# Loader.net
KiCad netlist of a schematic drawn in EAGLE
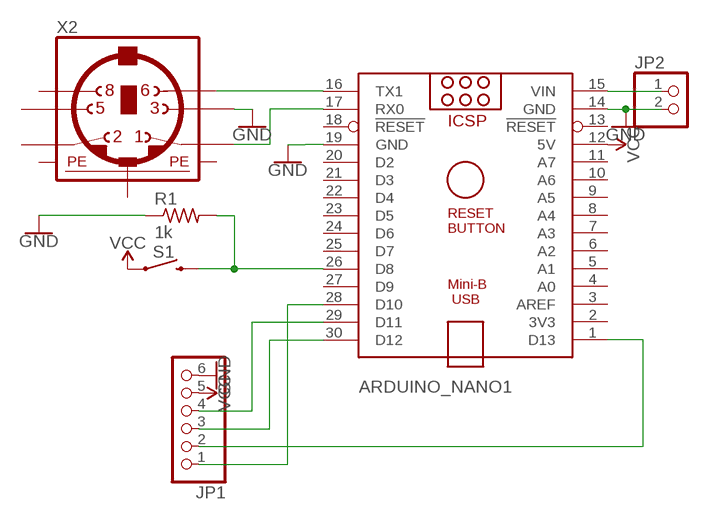
[diagram p0: schematic, sheet 1]

(export (version "E")
  (design (tool "Eeschema 10.0.6"))
  (components
    (comp (ref "ARDUINO_NANO1")
      (value "ARDUINO_NANO")
      (footprint "eagle-import:ARDUINO_NANO")
      (libsource (lib "eagle-import") (part "ARDUINO_NANO"))
    )
    (comp (ref "JP1")
      (value "PINHD-1X6")
      (footprint "eagle-import:1X06")
      (libsource (lib "eagle-import") (part "PINHD-1X6"))
    )
    (comp (ref "JP2")
      (value "PINHD-1X2")
      (footprint "eagle-import:1X02")
      (libsource (lib "eagle-import") (part "PINHD-1X2"))
    )
    (comp (ref "R1")
      (value "1k")
      (footprint "eagle-import:0204_7")
      (libsource (lib "eagle-import") (part "R-US_0204/7"))
    )
    (comp (ref "S1")
      (value "MOMENTARY-SWITCH-SPST-PTH-6.0MM")
      (footprint "eagle-import:TACTILE_SWITCH_PTH_6.0MM")
      (libsource (lib "eagle-import") (part "MOMENTARY-SWITCH-SPST-PTH-6.0MM"))
    )
    (comp (ref "X2")
      (value "MINI_DIN_6")
      (footprint "eagle-import:M_DIN6")
      (libsource (lib "eagle-import") (part "MINI_DIN_6"))
    )
  )
  (nets
    (net (code "1") (name "/PE1") (class "Default")
      (node (ref "X2") (pin "SH1") (pinfunction "PE1_SH1") (pintype "power_in"))
    )
    (net (code "2") (name "/PE2") (class "Default")
      (node (ref "X2") (pin "SH2") (pinfunction "PE2_SH2") (pintype "power_in"))
    )
    (net (code "3") (name "/PE3") (class "Default")
      (node (ref "X2") (pin "SH3") (pinfunction "PE3_SH3") (pintype "power_in"))
    )
    (net (code "4") (name "GND") (class "Default")
      (node (ref "ARDUINO_NANO1") (pin "14") (pinfunction "GND_14") (pintype "power_in"))
      (node (ref "ARDUINO_NANO1") (pin "19") (pinfunction "GND_19") (pintype "power_in"))
      (node (ref "JP1") (pin "6") (pinfunction "6_6") (pintype "passive"))
      (node (ref "JP2") (pin "2") (pinfunction "2_2") (pintype "passive"))
      (node (ref "R1") (pin "1") (pinfunction "1_1") (pintype "passive"))
      (node (ref "X2") (pin "3") (pinfunction "3_3") (pintype "passive"))
    )
    (net (code "5") (name "Net-(ARDUINO_NANO1-D8)") (class "Default")
      (node (ref "ARDUINO_NANO1") (pin "26") (pinfunction "D8_26") (pintype "bidirectional"))
      (node (ref "R1") (pin "2") (pinfunction "2_2") (pintype "passive"))
      (node (ref "S1") (pin "3") (pinfunction "2_3") (pintype "passive"))
    )
    (net (code "6") (name "Net-(ARDUINO_NANO1-D10)") (class "Default")
      (node (ref "ARDUINO_NANO1") (pin "28") (pinfunction "D10_28") (pintype "bidirectional"))
      (node (ref "JP1") (pin "1") (pinfunction "1_1") (pintype "passive"))
    )
    (net (code "7") (name "Net-(ARDUINO_NANO1-D11)") (class "Default")
      (node (ref "ARDUINO_NANO1") (pin "29") (pinfunction "D11_29") (pintype "bidirectional"))
      (node (ref "JP1") (pin "4") (pinfunction "4_4") (pintype "passive"))
    )
    (net (code "8") (name "Net-(ARDUINO_NANO1-D12)") (class "Default")
      (node (ref "ARDUINO_NANO1") (pin "30") (pinfunction "D12_30") (pintype "bidirectional"))
      (node (ref "JP1") (pin "3") (pinfunction "3_3") (pintype "passive"))
    )
    (net (code "9") (name "Net-(ARDUINO_NANO1-D13)") (class "Default")
      (node (ref "ARDUINO_NANO1") (pin "1") (pinfunction "D13_1") (pintype "bidirectional"))
      (node (ref "JP1") (pin "2") (pinfunction "2_2") (pintype "passive"))
    )
    (net (code "10") (name "Net-(ARDUINO_NANO1-RX0)") (class "Default")
      (node (ref "ARDUINO_NANO1") (pin "17") (pinfunction "RX0_17") (pintype "bidirectional"))
      (node (ref "X2") (pin "1") (pinfunction "1_1") (pintype "passive"))
    )
    (net (code "11") (name "Net-(ARDUINO_NANO1-TX1)") (class "Default")
      (node (ref "ARDUINO_NANO1") (pin "16") (pinfunction "TX1_16") (pintype "bidirectional"))
      (node (ref "X2") (pin "6") (pinfunction "6_6") (pintype "passive"))
    )
    (net (code "12") (name "Net-(ARDUINO_NANO1-VIN)") (class "Default")
      (node (ref "ARDUINO_NANO1") (pin "15") (pinfunction "VIN_15") (pintype "power_in"))
      (node (ref "JP2") (pin "1") (pinfunction "1_1") (pintype "passive"))
    )
    (net (code "13") (name "VCC") (class "Default")
      (node (ref "ARDUINO_NANO1") (pin "12") (pinfunction "5V_12") (pintype "power_in"))
      (node (ref "JP1") (pin "5") (pinfunction "5_5") (pintype "passive"))
      (node (ref "S1") (pin "1") (pinfunction "1_1") (pintype "passive"))
    )
    (net (code "14") (name "unconnected-(ARDUINO_NANO1-3V3-Pad2)") (class "Default")
      (node (ref "ARDUINO_NANO1") (pin "2") (pinfunction "3V3_2") (pintype "output"))
    )
    (net (code "15") (name "unconnected-(ARDUINO_NANO1-A0-Pad4)") (class "Default")
      (node (ref "ARDUINO_NANO1") (pin "4") (pinfunction "A0_4") (pintype "bidirectional"))
    )
    (net (code "16") (name "unconnected-(ARDUINO_NANO1-A1-Pad5)") (class "Default")
      (node (ref "ARDUINO_NANO1") (pin "5") (pinfunction "A1_5") (pintype "bidirectional"))
    )
    (net (code "17") (name "unconnected-(ARDUINO_NANO1-A2-Pad6)") (class "Default")
      (node (ref "ARDUINO_NANO1") (pin "6") (pinfunction "A2_6") (pintype "bidirectional"))
    )
    (net (code "18") (name "unconnected-(ARDUINO_NANO1-A3-Pad7)") (class "Default")
      (node (ref "ARDUINO_NANO1") (pin "7") (pinfunction "A3_7") (pintype "bidirectional"))
    )
    (net (code "19") (name "unconnected-(ARDUINO_NANO1-A4-Pad8)") (class "Default")
      (node (ref "ARDUINO_NANO1") (pin "8") (pinfunction "A4_8") (pintype "bidirectional"))
    )
    (net (code "20") (name "unconnected-(ARDUINO_NANO1-A5-Pad9)") (class "Default")
      (node (ref "ARDUINO_NANO1") (pin "9") (pinfunction "A5_9") (pintype "bidirectional"))
    )
    (net (code "21") (name "unconnected-(ARDUINO_NANO1-A6-Pad10)") (class "Default")
      (node (ref "ARDUINO_NANO1") (pin "10") (pinfunction "A6_10") (pintype "bidirectional"))
    )
    (net (code "22") (name "unconnected-(ARDUINO_NANO1-A7-Pad11)") (class "Default")
      (node (ref "ARDUINO_NANO1") (pin "11") (pinfunction "A7_11") (pintype "bidirectional"))
    )
    (net (code "23") (name "unconnected-(ARDUINO_NANO1-AREF-Pad3)") (class "Default")
      (node (ref "ARDUINO_NANO1") (pin "3") (pinfunction "AREF_3") (pintype "input"))
    )
    (net (code "24") (name "unconnected-(ARDUINO_NANO1-D2-Pad20)") (class "Default")
      (node (ref "ARDUINO_NANO1") (pin "20") (pinfunction "D2_20") (pintype "bidirectional"))
    )
    (net (code "25") (name "unconnected-(ARDUINO_NANO1-D3-Pad21)") (class "Default")
      (node (ref "ARDUINO_NANO1") (pin "21") (pinfunction "D3_21") (pintype "bidirectional"))
    )
    (net (code "26") (name "unconnected-(ARDUINO_NANO1-D4-Pad22)") (class "Default")
      (node (ref "ARDUINO_NANO1") (pin "22") (pinfunction "D4_22") (pintype "bidirectional"))
    )
    (net (code "27") (name "unconnected-(ARDUINO_NANO1-D5-Pad23)") (class "Default")
      (node (ref "ARDUINO_NANO1") (pin "23") (pinfunction "D5_23") (pintype "bidirectional"))
    )
    (net (code "28") (name "unconnected-(ARDUINO_NANO1-D6-Pad24)") (class "Default")
      (node (ref "ARDUINO_NANO1") (pin "24") (pinfunction "D6_24") (pintype "bidirectional"))
    )
    (net (code "29") (name "unconnected-(ARDUINO_NANO1-D7-Pad25)") (class "Default")
      (node (ref "ARDUINO_NANO1") (pin "25") (pinfunction "D7_25") (pintype "bidirectional"))
    )
    (net (code "30") (name "unconnected-(ARDUINO_NANO1-D9-Pad27)") (class "Default")
      (node (ref "ARDUINO_NANO1") (pin "27") (pinfunction "D9_27") (pintype "bidirectional"))
    )
    (net (code "31") (name "unconnected-(ARDUINO_NANO1-~{RESET}-Pad13)") (class "Default")
      (node (ref "ARDUINO_NANO1") (pin "13") (pinfunction "~{RESET}_13") (pintype "input"))
    )
    (net (code "32") (name "unconnected-(ARDUINO_NANO1-~{RESET}-Pad18)") (class "Default")
      (node (ref "ARDUINO_NANO1") (pin "18") (pinfunction "~{RESET}_18") (pintype "input"))
    )
    (net (code "33") (name "unconnected-(X2-Pad2)") (class "Default")
      (node (ref "X2") (pin "2") (pinfunction "2_2") (pintype "passive"))
    )
    (net (code "34") (name "unconnected-(X2-Pad5)") (class "Default")
      (node (ref "X2") (pin "5") (pinfunction "5_5") (pintype "passive"))
    )
    (net (code "35") (name "unconnected-(X2-Pad8)") (class "Default")
      (node (ref "X2") (pin "8") (pinfunction "8_8") (pintype "passive"))
    )
  )
)
